# FoneAstra3_2.net
KiCad netlist of a schematic drawn in EAGLE
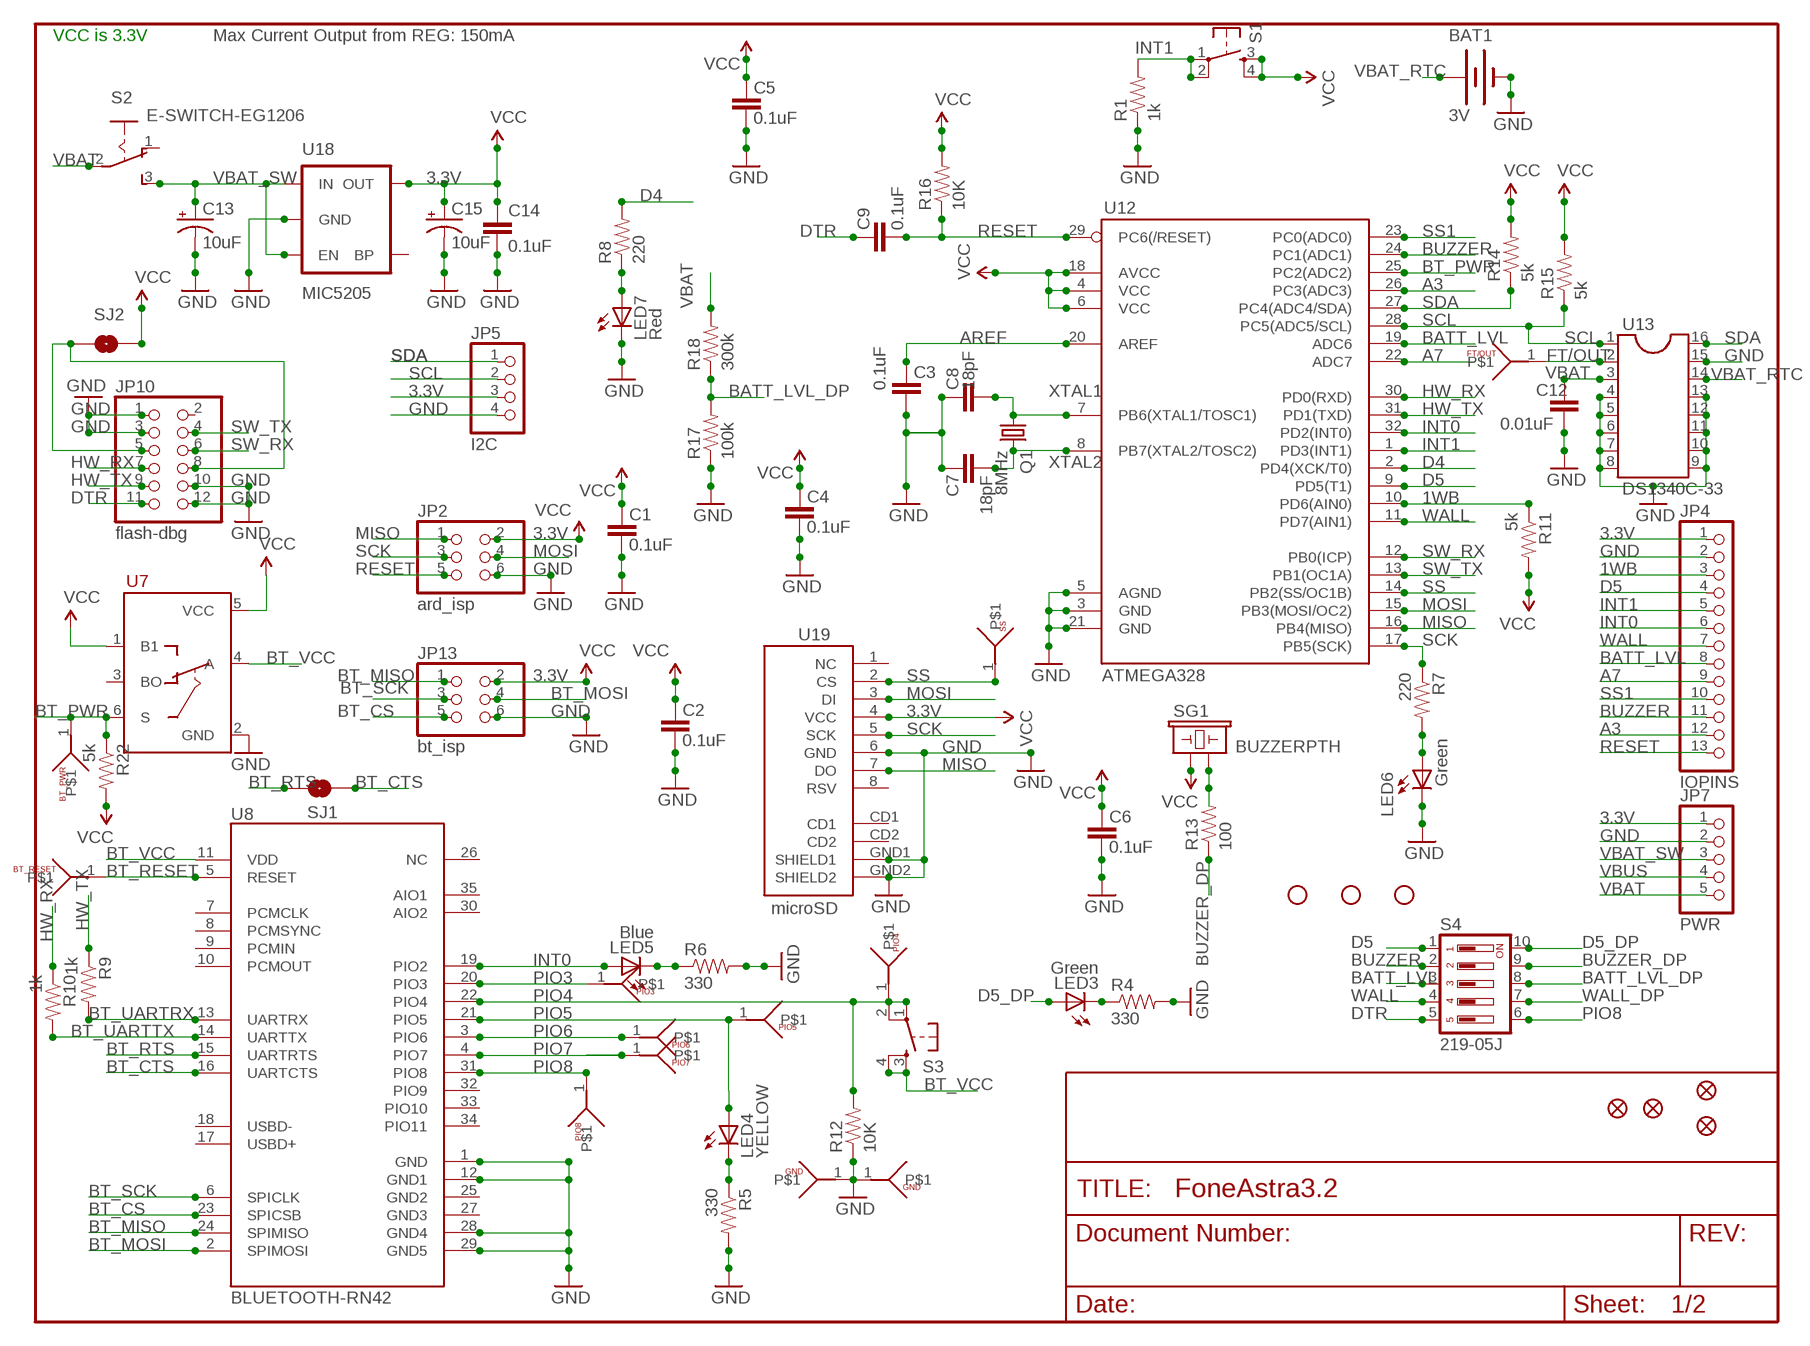
[diagram p0: schematic, sheet 1, part 1 of 2]
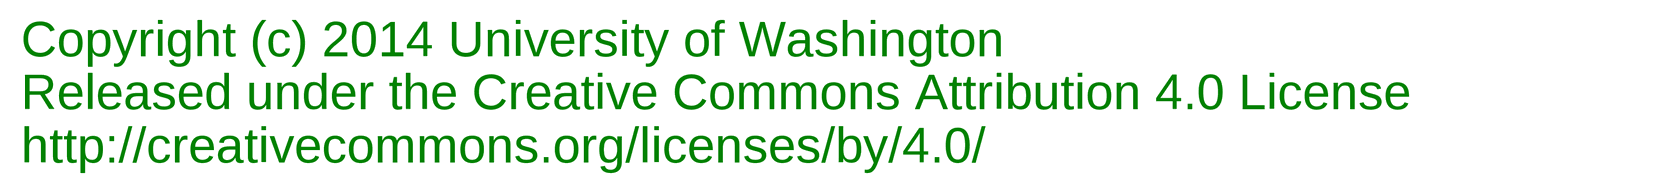
[diagram p1: schematic, sheet 1, part 2 of 2]
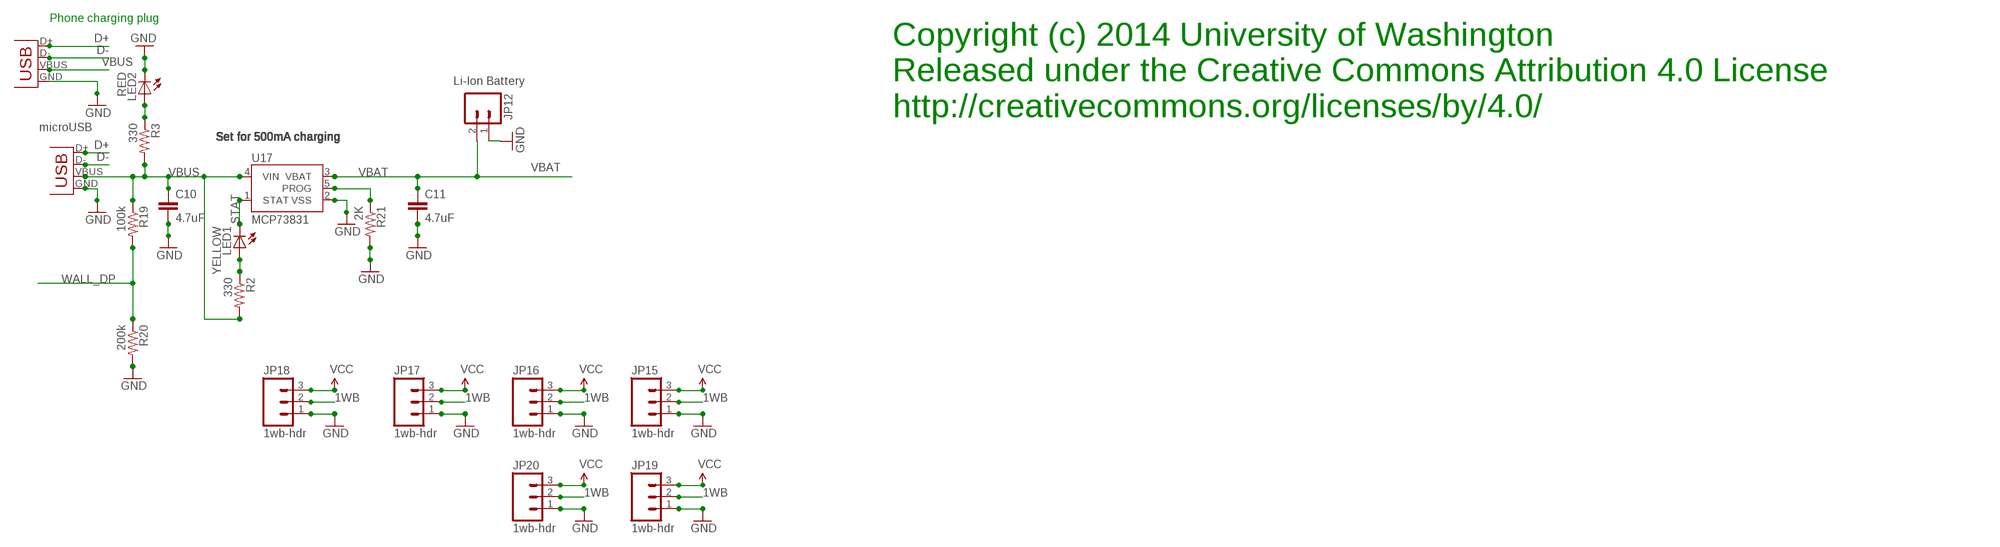
[diagram p2: schematic, sheet 2]

(export (version "E")
  (design (tool "Eeschema 10.0.6"))
  (components
    (comp (ref "C10")
      (value "4.7uF")
      (footprint "eagle-import:0402-CAP")
      (libsource (lib "eagle-import") (part "CAP0402-CAP"))
    )
    (comp (ref "C11")
      (value "4.7uF")
      (footprint "eagle-import:0402-CAP")
      (libsource (lib "eagle-import") (part "CAP0402-CAP"))
    )
    (comp (ref "JP12")
      (value "Li-Ion Battery")
      (footprint "eagle-import:SPARKFUN_JST-2-PTH")
      (libsource (lib "eagle-import") (part "SPARKFUN_M02JST-PTH-2"))
    )
    (comp (ref "JP15")
      (value "1wb-hdr")
      (footprint "eagle-import:JST-3-PTH")
      (libsource (lib "eagle-import") (part "M03JST-PTH"))
    )
    (comp (ref "JP16")
      (value "1wb-hdr")
      (footprint "eagle-import:JST-3-PTH")
      (libsource (lib "eagle-import") (part "M03JST-PTH"))
    )
    (comp (ref "JP17")
      (value "1wb-hdr")
      (footprint "eagle-import:JST-3-PTH")
      (libsource (lib "eagle-import") (part "M03JST-PTH"))
    )
    (comp (ref "JP18")
      (value "1wb-hdr")
      (footprint "eagle-import:JST-3-PTH")
      (libsource (lib "eagle-import") (part "M03JST-PTH"))
    )
    (comp (ref "JP19")
      (value "1wb-hdr")
      (footprint "eagle-import:JST-3-PTH")
      (libsource (lib "eagle-import") (part "M03JST-PTH"))
    )
    (comp (ref "JP20")
      (value "1wb-hdr")
      (footprint "eagle-import:JST-3-PTH")
      (libsource (lib "eagle-import") (part "M03JST-PTH"))
    )
    (comp (ref "LED1")
      (value "YELLOW")
      (footprint "eagle-import:LED-0603")
      (libsource (lib "eagle-import") (part "LED0603"))
    )
    (comp (ref "LED2")
      (value "RED")
      (footprint "eagle-import:LED-0603")
      (libsource (lib "eagle-import") (part "LED0603"))
    )
    (comp (ref "R2")
      (value "330")
      (footprint "eagle-import:0402-RES")
      (libsource (lib "eagle-import") (part "RESISTOR0402-RES"))
    )
    (comp (ref "R3")
      (value "330")
      (footprint "eagle-import:0402-RES")
      (libsource (lib "eagle-import") (part "RESISTOR0402-RES"))
    )
    (comp (ref "R19")
      (value "100k")
      (footprint "eagle-import:0402-RES")
      (libsource (lib "eagle-import") (part "RESISTOR0402-RES"))
    )
    (comp (ref "R20")
      (value "200k")
      (footprint "eagle-import:0402-RES")
      (libsource (lib "eagle-import") (part "RESISTOR0402-RES"))
    )
    (comp (ref "R21")
      (value "2K")
      (footprint "eagle-import:0402-RES")
      (libsource (lib "eagle-import") (part "RESISTOR0402-RES"))
    )
    (comp (ref "U17")
      (value "MCP73831")
      (footprint "eagle-import:SOT23-5")
      (libsource (lib "eagle-import") (part "MCP73831"))
    )
    (comp (ref "X1")
      (value "Micro USB")
      (footprint "eagle-import:USB-MICROB")
      (libsource (lib "eagle-import") (part "USB-MICROB"))
    )
    (comp (ref "X2")
      (value "Micro USB")
      (footprint "eagle-import:USB-MICROB")
      (libsource (lib "eagle-import") (part "USB-MICROB"))
    )
    (comp (ref "$$U3")
      (value "BT_RESET")
      (footprint "eagle-import:TESTPOINT")
      (libsource (lib "eagle-import") (part "TESTPOINT"))
    )
    (comp (ref "$$U4")
      (value "PIO6")
      (footprint "eagle-import:TESTPOINT")
      (libsource (lib "eagle-import") (part "TESTPOINT"))
    )
    (comp (ref "$$U5")
      (value "PIO7")
      (footprint "eagle-import:TESTPOINT")
      (libsource (lib "eagle-import") (part "TESTPOINT"))
    )
    (comp (ref "$$U6")
      (value "GND")
      (footprint "eagle-import:TESTPOINT")
      (libsource (lib "eagle-import") (part "TESTPOINT"))
    )
    (comp (ref "$$U9")
      (value "PIO4")
      (footprint "eagle-import:TESTPOINT")
      (libsource (lib "eagle-import") (part "TESTPOINT"))
    )
    (comp (ref "$$U10")
      (value "PIO3")
      (footprint "eagle-import:TESTPOINT")
      (libsource (lib "eagle-import") (part "TESTPOINT"))
    )
    (comp (ref "$$U11")
      (value "PIO5")
      (footprint "eagle-import:TESTPOINT")
      (libsource (lib "eagle-import") (part "TESTPOINT"))
    )
    (comp (ref "$$U15")
      (value "FT/OUT")
      (footprint "eagle-import:TESTPOINT")
      (libsource (lib "eagle-import") (part "TESTPOINT"))
    )
    (comp (ref "$$U16")
      (value "GND")
      (footprint "eagle-import:TESTPOINT")
      (libsource (lib "eagle-import") (part "TESTPOINT"))
    )
    (comp (ref "BAT1")
      (value "3V")
      (footprint "eagle-import:BATTCON_12MM_CURVED")
      (libsource (lib "eagle-import") (part "BATTERY"))
    )
    (comp (ref "BT_PWR")
      (value "BT_PWR")
      (footprint "eagle-import:TESTPOINT")
      (libsource (lib "eagle-import") (part "TESTPOINT"))
    )
    (comp (ref "C1")
      (value "0.1uF")
      (footprint "eagle-import:0402-CAP")
      (libsource (lib "eagle-import") (part "CAP0402-CAP"))
    )
    (comp (ref "C2")
      (value "0.1uF")
      (footprint "eagle-import:0402-CAP")
      (libsource (lib "eagle-import") (part "CAP0402-CAP"))
    )
    (comp (ref "C3")
      (value "0.1uF")
      (footprint "eagle-import:0402-CAP")
      (libsource (lib "eagle-import") (part "CAP0402-CAP"))
    )
    (comp (ref "C4")
      (value "0.1uF")
      (footprint "eagle-import:0402-CAP")
      (libsource (lib "eagle-import") (part "CAP0402-CAP"))
    )
    (comp (ref "C5")
      (value "0.1uF")
      (footprint "eagle-import:0402-CAP")
      (libsource (lib "eagle-import") (part "CAP0402-CAP"))
    )
    (comp (ref "C6")
      (value "0.1uF")
      (footprint "eagle-import:0402-CAP")
      (libsource (lib "eagle-import") (part "CAP0402-CAP"))
    )
    (comp (ref "C7")
      (value "18pF")
      (footprint "eagle-import:0402-CAP")
      (libsource (lib "eagle-import") (part "CAP0402-CAP"))
    )
    (comp (ref "C8")
      (value "18pF")
      (footprint "eagle-import:0402-CAP")
      (libsource (lib "eagle-import") (part "CAP0402-CAP"))
    )
    (comp (ref "C9")
      (value "0.1uF")
      (footprint "eagle-import:0402-CAP")
      (libsource (lib "eagle-import") (part "CAP0402-CAP"))
    )
    (comp (ref "C12")
      (value "0.01uF")
      (footprint "eagle-import:0402-CAP")
      (libsource (lib "eagle-import") (part "CAP0402-CAP"))
    )
    (comp (ref "C13")
      (value "10uF")
      (footprint "eagle-import:EIA3216")
      (libsource (lib "eagle-import") (part "CAP_POL1206"))
    )
    (comp (ref "C14")
      (value "0.1uF")
      (footprint "eagle-import:0402-CAP")
      (libsource (lib "eagle-import") (part "CAP0402-CAP"))
    )
    (comp (ref "C15")
      (value "10uF")
      (footprint "eagle-import:EIA3216")
      (libsource (lib "eagle-import") (part "CAP_POL1206"))
    )
    (comp (ref "JP1")
      (value "SPARKFUN_FIDUCIAL1.5X3")
      (footprint "eagle-import:SPARKFUN_FIDUCIAL-1.5X3")
      (libsource (lib "eagle-import") (part "SPARKFUN_FIDUCIAL1.5X3"))
    )
    (comp (ref "JP2")
      (value "ard_isp")
      (footprint "eagle-import:2X03")
      (libsource (lib "eagle-import") (part "PINHD-2X3"))
    )
    (comp (ref "JP3")
      (value "STAND-OFFTIGHT")
      (footprint "eagle-import:STAND-OFF-TIGHT")
      (libsource (lib "eagle-import") (part "STAND-OFFTIGHT"))
    )
    (comp (ref "JP4")
      (value "IOPINS")
      (footprint "eagle-import:1X13M")
      (libsource (lib "eagle-import") (part "PINHD-1X13M"))
    )
    (comp (ref "JP5")
      (value "I2C")
      (footprint "eagle-import:1X04M")
      (libsource (lib "eagle-import") (part "PINHD-1X4M"))
    )
    (comp (ref "JP6")
      (value "STAND-OFFTIGHT")
      (footprint "eagle-import:STAND-OFF-TIGHT")
      (libsource (lib "eagle-import") (part "STAND-OFFTIGHT"))
    )
    (comp (ref "JP7")
      (value "PWR")
      (footprint "eagle-import:1X05M")
      (libsource (lib "eagle-import") (part "PINHD-1X5M"))
    )
    (comp (ref "JP8")
      (value "SPARKFUN_FIDUCIAL1.5X3")
      (footprint "eagle-import:SPARKFUN_FIDUCIAL-1.5X3")
      (libsource (lib "eagle-import") (part "SPARKFUN_FIDUCIAL1.5X3"))
    )
    (comp (ref "JP9")
      (value "STAND-OFFTIGHT")
      (footprint "eagle-import:STAND-OFF-TIGHT")
      (libsource (lib "eagle-import") (part "STAND-OFFTIGHT"))
    )
    (comp (ref "JP10")
      (value "flash-dbg")
      (footprint "eagle-import:2X06")
      (libsource (lib "eagle-import") (part "PINHD-2X6"))
    )
    (comp (ref "JP11")
      (value "SPARKFUN_FIDUCIAL1.5X3")
      (footprint "eagle-import:SPARKFUN_FIDUCIAL-1.5X3")
      (libsource (lib "eagle-import") (part "SPARKFUN_FIDUCIAL1.5X3"))
    )
    (comp (ref "JP13")
      (value "bt_isp")
      (footprint "eagle-import:2X03")
      (libsource (lib "eagle-import") (part "PINHD-2X3"))
    )
    (comp (ref "JP14")
      (value "SPARKFUN_FIDUCIAL1.5X3")
      (footprint "eagle-import:SPARKFUN_FIDUCIAL-1.5X3")
      (libsource (lib "eagle-import") (part "SPARKFUN_FIDUCIAL1.5X3"))
    )
    (comp (ref "LED3")
      (value "Green")
      (footprint "eagle-import:LED-0603")
      (libsource (lib "eagle-import") (part "LED0603"))
    )
    (comp (ref "LED4")
      (value "YELLOW")
      (footprint "eagle-import:LED-0603")
      (libsource (lib "eagle-import") (part "LED0603"))
    )
    (comp (ref "LED5")
      (value "Blue")
      (footprint "eagle-import:LED-0603")
      (libsource (lib "eagle-import") (part "LED0603"))
    )
    (comp (ref "LED6")
      (value "Green")
      (footprint "eagle-import:LED-0603")
      (libsource (lib "eagle-import") (part "LED0603"))
    )
    (comp (ref "LED7")
      (value "Red")
      (footprint "eagle-import:LED-0603")
      (libsource (lib "eagle-import") (part "LED0603"))
    )
    (comp (ref "PIO8")
      (value "PIO8")
      (footprint "eagle-import:TESTPOINT")
      (libsource (lib "eagle-import") (part "TESTPOINT"))
    )
    (comp (ref "Q1")
      (value "8MHz")
      (footprint "eagle-import:HC49_S")
      (libsource (lib "eagle-import") (part "CRYSTALHC49S"))
    )
    (comp (ref "R1")
      (value "1k")
      (footprint "eagle-import:0402-RES")
      (libsource (lib "eagle-import") (part "RESISTOR0402-RES"))
    )
    (comp (ref "R4")
      (value "330")
      (footprint "eagle-import:0402-RES")
      (libsource (lib "eagle-import") (part "RESISTOR0402-RES"))
    )
    (comp (ref "R5")
      (value "330")
      (footprint "eagle-import:0402-RES")
      (libsource (lib "eagle-import") (part "RESISTOR0402-RES"))
    )
    (comp (ref "R6")
      (value "330")
      (footprint "eagle-import:0402-RES")
      (libsource (lib "eagle-import") (part "RESISTOR0402-RES"))
    )
    (comp (ref "R7")
      (value "220")
      (footprint "eagle-import:0402-RES")
      (libsource (lib "eagle-import") (part "RESISTOR0402-RES"))
    )
    (comp (ref "R8")
      (value "220")
      (footprint "eagle-import:0402-RES")
      (libsource (lib "eagle-import") (part "RESISTOR0402-RES"))
    )
    (comp (ref "R9")
      (value "1k")
      (footprint "eagle-import:0402-RES")
      (libsource (lib "eagle-import") (part "RESISTOR0402-RES"))
    )
    (comp (ref "R10")
      (value "1k")
      (footprint "eagle-import:0402-RES")
      (libsource (lib "eagle-import") (part "RESISTOR0402-RES"))
    )
    (comp (ref "R11")
      (value "5k")
      (footprint "eagle-import:0402-RES")
      (libsource (lib "eagle-import") (part "RESISTOR0402-RES"))
    )
    (comp (ref "R12")
      (value "10K")
      (footprint "eagle-import:0402-RES")
      (libsource (lib "eagle-import") (part "RESISTOR0402-RES"))
    )
    (comp (ref "R13")
      (value "100")
      (footprint "eagle-import:0402-RES")
      (libsource (lib "eagle-import") (part "RESISTOR0402-RES"))
    )
    (comp (ref "R14")
      (value "5k")
      (footprint "eagle-import:0402-RES")
      (libsource (lib "eagle-import") (part "RESISTOR0402-RES"))
    )
    (comp (ref "R15")
      (value "5k")
      (footprint "eagle-import:0402-RES")
      (libsource (lib "eagle-import") (part "RESISTOR0402-RES"))
    )
    (comp (ref "R16")
      (value "10K")
      (footprint "eagle-import:0402-RES")
      (libsource (lib "eagle-import") (part "RESISTOR0402-RES"))
    )
    (comp (ref "R17")
      (value "100k")
      (footprint "eagle-import:0402-RES")
      (libsource (lib "eagle-import") (part "RESISTOR0402-RES"))
    )
    (comp (ref "R18")
      (value "300k")
      (footprint "eagle-import:0402-RES")
      (libsource (lib "eagle-import") (part "RESISTOR0402-RES"))
    )
    (comp (ref "R22")
      (value "5k")
      (footprint "eagle-import:0402-RES")
      (libsource (lib "eagle-import") (part "RESISTOR0402-RES"))
    )
    (comp (ref "S1")
      (value "switch")
      (footprint "eagle-import:SPARKFUN_TACTILE-PTH")
      (libsource (lib "eagle-import") (part "SPARKFUN_TAC_SWITCHPTH"))
    )
    (comp (ref "S2")
      (value "E-SWITCH-EG1206")
      (footprint "eagle-import:EG1206")
      (libsource (lib "eagle-import") (part "E-SWITCH-EG1206"))
    )
    (comp (ref "S3")
      (value "Reset")
      (footprint "eagle-import:TACTILE_SWITCH_SMD")
      (libsource (lib "eagle-import") (part "TAC_SWITCHSMD"))
    )
    (comp (ref "S4")
      (value "219-05J")
      (footprint "eagle-import:CTS-219-05J")
      (libsource (lib "eagle-import") (part "219-05J"))
    )
    (comp (ref "SG1")
      (value "BUZZERPTH")
      (footprint "eagle-import:BUZZER-12MM")
      (libsource (lib "eagle-import") (part "BUZZERPTH"))
    )
    (comp (ref "SJ1")
      (value "SOLDERJUMPERNC2")
      (footprint "eagle-import:SJ_2S-NOTRACE")
      (libsource (lib "eagle-import") (part "SOLDERJUMPERNC2"))
    )
    (comp (ref "SJ2")
      (value "SOLDERJUMPERNC2")
      (footprint "eagle-import:SJ_2S-NOTRACE")
      (libsource (lib "eagle-import") (part "SOLDERJUMPERNC2"))
    )
    (comp (ref "SS")
      (value "SS")
      (footprint "eagle-import:TESTPOINT")
      (libsource (lib "eagle-import") (part "TESTPOINT"))
    )
    (comp (ref "U7")
      (value "FSA4157AP6X")
      (footprint "eagle-import:SC70-6")
      (libsource (lib "eagle-import") (part "FSA4157AP6X"))
    )
    (comp (ref "U8")
      (value "BLUETOOTH-RN42")
      (footprint "eagle-import:RN41")
      (libsource (lib "eagle-import") (part "BLUETOOTH-RN41{dblquote}"))
    )
    (comp (ref "U12")
      (value "ATMEGA328")
      (footprint "eagle-import:TQFP32-08")
      (libsource (lib "eagle-import") (part "ATMEGA168"))
    )
    (comp (ref "U13")
      (value "DS1340C-33")
      (footprint "eagle-import:SO16L")
      (libsource (lib "eagle-import") (part "DS1340C-33"))
    )
    (comp (ref "U18")
      (value "MIC5205")
      (footprint "eagle-import:SOT23-5")
      (libsource (lib "eagle-import") (part "V_REG_LDOSMD"))
    )
    (comp (ref "U19")
      (value "microSD")
      (footprint "eagle-import:MICRO-SD-SOCKET-PP")
      (libsource (lib "eagle-import") (part "USD-SOCKETSMD"))
    )
  )
  (nets
    (net (code "1") (name "1WB") (class "Default")
      (node (ref "JP15") (pin "2") (pinfunction "2_2") (pintype "passive"))
      (node (ref "JP16") (pin "2") (pinfunction "2_2") (pintype "passive"))
      (node (ref "JP17") (pin "2") (pinfunction "2_2") (pintype "passive"))
      (node (ref "JP18") (pin "2") (pinfunction "2_2") (pintype "passive"))
      (node (ref "JP19") (pin "2") (pinfunction "2_2") (pintype "passive"))
      (node (ref "JP20") (pin "2") (pinfunction "2_2") (pintype "passive"))
      (node (ref "JP4") (pin "3") (pinfunction "3_3") (pintype "passive"))
      (node (ref "R11") (pin "1") (pinfunction "1_1") (pintype "passive"))
      (node (ref "U12") (pin "10") (pinfunction "PD6(AIN0)_10") (pintype "bidirectional"))
    )
    (net (code "2") (name "3.3V") (class "Default")
      (node (ref "C1") (pin "2") (pinfunction "2_2") (pintype "passive"))
      (node (ref "C14") (pin "1") (pinfunction "1_1") (pintype "passive"))
      (node (ref "C15") (pin "A") (pinfunction "+_A") (pintype "passive"))
      (node (ref "C2") (pin "2") (pinfunction "2_2") (pintype "passive"))
      (node (ref "C4") (pin "2") (pinfunction "2_2") (pintype "passive"))
      (node (ref "C5") (pin "2") (pinfunction "2_2") (pintype "passive"))
      (node (ref "C6") (pin "2") (pinfunction "2_2") (pintype "passive"))
      (node (ref "JP13") (pin "2") (pinfunction "2_2") (pintype "passive"))
      (node (ref "JP15") (pin "3") (pinfunction "3_3") (pintype "passive"))
      (node (ref "JP16") (pin "3") (pinfunction "3_3") (pintype "passive"))
      (node (ref "JP17") (pin "3") (pinfunction "3_3") (pintype "passive"))
      (node (ref "JP18") (pin "3") (pinfunction "3_3") (pintype "passive"))
      (node (ref "JP19") (pin "3") (pinfunction "3_3") (pintype "passive"))
      (node (ref "JP2") (pin "2") (pinfunction "2_2") (pintype "passive"))
      (node (ref "JP20") (pin "3") (pinfunction "3_3") (pintype "passive"))
      (node (ref "JP4") (pin "1") (pinfunction "1_1") (pintype "passive"))
      (node (ref "JP5") (pin "3") (pinfunction "3_3") (pintype "passive"))
      (node (ref "JP7") (pin "1") (pinfunction "1_1") (pintype "passive"))
      (node (ref "R11") (pin "2") (pinfunction "2_2") (pintype "passive"))
      (node (ref "R14") (pin "2") (pinfunction "2_2") (pintype "passive"))
      (node (ref "R15") (pin "2") (pinfunction "2_2") (pintype "passive"))
      (node (ref "R16") (pin "2") (pinfunction "2_2") (pintype "passive"))
      (node (ref "R22") (pin "2") (pinfunction "2_2") (pintype "passive"))
      (node (ref "S1") (pin "3") (pinfunction "3_3") (pintype "passive"))
      (node (ref "S1") (pin "4") (pinfunction "4_4") (pintype "passive"))
      (node (ref "SG1") (pin "+") (pinfunction "1_+") (pintype "passive"))
      (node (ref "SJ2") (pin "1") (pinfunction "1_1") (pintype "passive"))
      (node (ref "U12") (pin "18") (pinfunction "AVCC_18") (pintype "bidirectional"))
      (node (ref "U12") (pin "4") (pinfunction "VCC_4") (pintype "bidirectional"))
      (node (ref "U12") (pin "6") (pinfunction "VCC_6") (pintype "bidirectional"))
      (node (ref "U18") (pin "5") (pinfunction "OUT_5") (pintype "passive"))
      (node (ref "U19") (pin "4") (pinfunction "VCC_4") (pintype "bidirectional"))
      (node (ref "U7") (pin "1") (pinfunction "B1_1") (pintype "passive"))
      (node (ref "U7") (pin "5") (pinfunction "VCC_5") (pintype "power_in"))
    )
    (net (code "3") (name "A3") (class "Default")
      (node (ref "JP4") (pin "12") (pinfunction "12_12") (pintype "passive"))
      (node (ref "U12") (pin "26") (pinfunction "PC3(ADC3)_26") (pintype "bidirectional"))
    )
    (net (code "4") (name "A7") (class "Default")
      (node (ref "JP4") (pin "9") (pinfunction "9_9") (pintype "passive"))
      (node (ref "U12") (pin "22") (pinfunction "ADC7_22") (pintype "bidirectional"))
    )
    (net (code "5") (name "AREF") (class "Default")
      (node (ref "C3") (pin "2") (pinfunction "2_2") (pintype "passive"))
      (node (ref "U12") (pin "20") (pinfunction "AREF_20") (pintype "bidirectional"))
    )
    (net (code "6") (name "BATT_LVL") (class "Default")
      (node (ref "JP4") (pin "8") (pinfunction "8_8") (pintype "passive"))
      (node (ref "S4") (pin "3") (pinfunction "3_3") (pintype "passive"))
      (node (ref "U12") (pin "19") (pinfunction "ADC6_19") (pintype "bidirectional"))
    )
    (net (code "7") (name "BATT_LVL_DP") (class "Default")
      (node (ref "R17") (pin "2") (pinfunction "2_2") (pintype "passive"))
      (node (ref "R18") (pin "1") (pinfunction "1_1") (pintype "passive"))
      (node (ref "S4") (pin "8") (pinfunction "8_8") (pintype "passive"))
    )
    (net (code "8") (name "BT_CS") (class "Default")
      (node (ref "JP13") (pin "5") (pinfunction "5_5") (pintype "passive"))
      (node (ref "U8") (pin "23") (pinfunction "SPICSB_23") (pintype "bidirectional"))
    )
    (net (code "9") (name "BT_CTS") (class "Default")
      (node (ref "SJ1") (pin "1") (pinfunction "1_1") (pintype "passive"))
      (node (ref "U8") (pin "16") (pinfunction "UARTCTS_16") (pintype "bidirectional"))
    )
    (net (code "10") (name "BT_MISO") (class "Default")
      (node (ref "JP13") (pin "1") (pinfunction "1_1") (pintype "passive"))
      (node (ref "U8") (pin "24") (pinfunction "SPIMISO_24") (pintype "bidirectional"))
    )
    (net (code "11") (name "BT_MOSI") (class "Default")
      (node (ref "JP13") (pin "4") (pinfunction "4_4") (pintype "passive"))
      (node (ref "U8") (pin "2") (pinfunction "SPIMOSI_2") (pintype "bidirectional"))
    )
    (net (code "12") (name "BT_PWR") (class "Default")
      (node (ref "BT_PWR") (pin "1") (pinfunction "P$1_1") (pintype "bidirectional"))
      (node (ref "R22") (pin "1") (pinfunction "1_1") (pintype "passive"))
      (node (ref "U12") (pin "25") (pinfunction "PC2(ADC2)_25") (pintype "bidirectional"))
      (node (ref "U7") (pin "6") (pinfunction "S_6") (pintype "bidirectional"))
    )
    (net (code "13") (name "BT_RESET") (class "Default")
      (node (ref "$$U3") (pin "1") (pinfunction "P$1_1") (pintype "bidirectional"))
      (node (ref "U8") (pin "5") (pinfunction "RESET_5") (pintype "bidirectional"))
    )
    (net (code "14") (name "BT_RTS") (class "Default")
      (node (ref "SJ1") (pin "2") (pinfunction "2_2") (pintype "passive"))
      (node (ref "U8") (pin "15") (pinfunction "UARTRTS_15") (pintype "bidirectional"))
    )
    (net (code "15") (name "BT_SCK") (class "Default")
      (node (ref "JP13") (pin "3") (pinfunction "3_3") (pintype "passive"))
      (node (ref "U8") (pin "6") (pinfunction "SPICLK_6") (pintype "bidirectional"))
    )
    (net (code "16") (name "BT_UARTRX") (class "Default")
      (node (ref "R9") (pin "2") (pinfunction "2_2") (pintype "passive"))
      (node (ref "U8") (pin "13") (pinfunction "UARTRX_13") (pintype "bidirectional"))
    )
    (net (code "17") (name "BT_UARTTX") (class "Default")
      (node (ref "R10") (pin "2") (pinfunction "2_2") (pintype "passive"))
      (node (ref "U8") (pin "14") (pinfunction "UARTTX_14") (pintype "bidirectional"))
    )
    (net (code "18") (name "BT_VCC") (class "Default")
      (node (ref "S3") (pin "3") (pinfunction "3_3") (pintype "passive"))
      (node (ref "S3") (pin "4") (pinfunction "4_4") (pintype "passive"))
      (node (ref "U7") (pin "4") (pinfunction "A_4") (pintype "passive"))
      (node (ref "U8") (pin "11") (pinfunction "VDD_11") (pintype "bidirectional"))
    )
    (net (code "19") (name "BUZZER") (class "Default")
      (node (ref "JP4") (pin "11") (pinfunction "11_11") (pintype "passive"))
      (node (ref "S4") (pin "2") (pinfunction "2_2") (pintype "passive"))
      (node (ref "U12") (pin "24") (pinfunction "PC1(ADC1)_24") (pintype "bidirectional"))
    )
    (net (code "20") (name "BUZZER_DP") (class "Default")
      (node (ref "R13") (pin "1") (pinfunction "1_1") (pintype "passive"))
      (node (ref "S4") (pin "9") (pinfunction "9_9") (pintype "passive"))
    )
    (net (code "21") (name "D+") (class "Default")
      (node (ref "X1") (pin "D+") (pinfunction "D+_D+") (pintype "bidirectional"))
      (node (ref "X2") (pin "D+") (pinfunction "D+_D+") (pintype "bidirectional"))
    )
    (net (code "22") (name "D-") (class "Default")
      (node (ref "X1") (pin "D-") (pinfunction "D-_D-") (pintype "bidirectional"))
      (node (ref "X2") (pin "D-") (pinfunction "D-_D-") (pintype "bidirectional"))
    )
    (net (code "23") (name "D4") (class "Default")
      (node (ref "R8") (pin "2") (pinfunction "2_2") (pintype "passive"))
      (node (ref "U12") (pin "2") (pinfunction "PD4(XCK/T0)_2") (pintype "bidirectional"))
    )
    (net (code "24") (name "D5") (class "Default")
      (node (ref "JP4") (pin "4") (pinfunction "4_4") (pintype "passive"))
      (node (ref "S4") (pin "1") (pinfunction "1_1") (pintype "passive"))
      (node (ref "U12") (pin "9") (pinfunction "PD5(T1)_9") (pintype "bidirectional"))
    )
    (net (code "25") (name "D5_DP") (class "Default")
      (node (ref "LED3") (pin "A") (pinfunction "A_A") (pintype "passive"))
      (node (ref "S4") (pin "10") (pinfunction "10_10") (pintype "passive"))
    )
    (net (code "26") (name "DTR") (class "Default")
      (node (ref "C9") (pin "2") (pinfunction "2_2") (pintype "passive"))
      (node (ref "JP10") (pin "11") (pinfunction "11_11") (pintype "passive"))
      (node (ref "S4") (pin "5") (pinfunction "5_5") (pintype "passive"))
    )
    (net (code "27") (name "FT{slash}OUT") (class "Default")
      (node (ref "$$U15") (pin "1") (pinfunction "P$1_1") (pintype "bidirectional"))
      (node (ref "U13") (pin "2") (pinfunction "2_2") (pintype "passive"))
    )
    (net (code "28") (name "GND") (class "Default")
      (node (ref "$$U16") (pin "1") (pinfunction "P$1_1") (pintype "bidirectional"))
      (node (ref "$$U6") (pin "1") (pinfunction "P$1_1") (pintype "bidirectional"))
      (node (ref "BAT1") (pin "GND") (pinfunction "-_GND") (pintype "power_in"))
      (node (ref "C1") (pin "1") (pinfunction "1_1") (pintype "passive"))
      (node (ref "C10") (pin "2") (pinfunction "2_2") (pintype "passive"))
      (node (ref "C11") (pin "2") (pinfunction "2_2") (pintype "passive"))
      (node (ref "C12") (pin "1") (pinfunction "1_1") (pintype "passive"))
      (node (ref "C13") (pin "C") (pinfunction "-_C") (pintype "passive"))
      (node (ref "C14") (pin "2") (pinfunction "2_2") (pintype "passive"))
      (node (ref "C15") (pin "C") (pinfunction "-_C") (pintype "passive"))
      (node (ref "C2") (pin "1") (pinfunction "1_1") (pintype "passive"))
      (node (ref "C3") (pin "1") (pinfunction "1_1") (pintype "passive"))
      (node (ref "C4") (pin "1") (pinfunction "1_1") (pintype "passive"))
      (node (ref "C5") (pin "1") (pinfunction "1_1") (pintype "passive"))
      (node (ref "C6") (pin "1") (pinfunction "1_1") (pintype "passive"))
      (node (ref "C7") (pin "2") (pinfunction "2_2") (pintype "passive"))
      (node (ref "C8") (pin "2") (pinfunction "2_2") (pintype "passive"))
      (node (ref "JP10") (pin "1") (pinfunction "1_1") (pintype "passive"))
      (node (ref "JP10") (pin "10") (pinfunction "10_10") (pintype "passive"))
      (node (ref "JP10") (pin "12") (pinfunction "12_12") (pintype "passive"))
      (node (ref "JP10") (pin "3") (pinfunction "3_3") (pintype "passive"))
      (node (ref "JP12") (pin "1") (pinfunction "1_1") (pintype "passive"))
      (node (ref "JP13") (pin "6") (pinfunction "6_6") (pintype "passive"))
      (node (ref "JP15") (pin "1") (pinfunction "1_1") (pintype "passive"))
      (node (ref "JP16") (pin "1") (pinfunction "1_1") (pintype "passive"))
      (node (ref "JP17") (pin "1") (pinfunction "1_1") (pintype "passive"))
      (node (ref "JP18") (pin "1") (pinfunction "1_1") (pintype "passive"))
      (node (ref "JP19") (pin "1") (pinfunction "1_1") (pintype "passive"))
      (node (ref "JP2") (pin "6") (pinfunction "6_6") (pintype "passive"))
      (node (ref "JP20") (pin "1") (pinfunction "1_1") (pintype "passive"))
      (node (ref "JP4") (pin "2") (pinfunction "2_2") (pintype "passive"))
      (node (ref "JP5") (pin "4") (pinfunction "4_4") (pintype "passive"))
      (node (ref "JP7") (pin "2") (pinfunction "2_2") (pintype "passive"))
      (node (ref "LED2") (pin "C") (pinfunction "C_C") (pintype "passive"))
      (node (ref "LED6") (pin "C") (pinfunction "C_C") (pintype "passive"))
      (node (ref "LED7") (pin "C") (pinfunction "C_C") (pintype "passive"))
      (node (ref "R1") (pin "1") (pinfunction "1_1") (pintype "passive"))
      (node (ref "R12") (pin "1") (pinfunction "1_1") (pintype "passive"))
      (node (ref "R17") (pin "1") (pinfunction "1_1") (pintype "passive"))
      (node (ref "R20") (pin "2") (pinfunction "2_2") (pintype "passive"))
      (node (ref "R21") (pin "2") (pinfunction "2_2") (pintype "passive"))
      (node (ref "R4") (pin "2") (pinfunction "2_2") (pintype "passive"))
      (node (ref "R5") (pin "2") (pinfunction "2_2") (pintype "passive"))
      (node (ref "R6") (pin "2") (pinfunction "2_2") (pintype "passive"))
      (node (ref "U12") (pin "21") (pinfunction "GND_21") (pintype "bidirectional"))
      (node (ref "U12") (pin "3") (pinfunction "GND_3") (pintype "bidirectional"))
      (node (ref "U12") (pin "5") (pinfunction "AGND_5") (pintype "bidirectional"))
      (node (ref "U13") (pin "10") (pinfunction "10_10") (pintype "passive"))
      (node (ref "U13") (pin "11") (pinfunction "11_11") (pintype "passive"))
      (node (ref "U13") (pin "12") (pinfunction "12_12") (pintype "passive"))
      (node (ref "U13") (pin "13") (pinfunction "13_13") (pintype "passive"))
      (node (ref "U13") (pin "15") (pinfunction "15_15") (pintype "passive"))
      (node (ref "U13") (pin "4") (pinfunction "4_4") (pintype "passive"))
      (node (ref "U13") (pin "5") (pinfunction "5_5") (pintype "passive"))
      (node (ref "U13") (pin "6") (pinfunction "6_6") (pintype "passive"))
      (node (ref "U13") (pin "7") (pinfunction "7_7") (pintype "passive"))
      (node (ref "U13") (pin "8") (pinfunction "8_8") (pintype "passive"))
      (node (ref "U13") (pin "9") (pinfunction "9_9") (pintype "passive"))
      (node (ref "U17") (pin "2") (pinfunction "VSS_2") (pintype "power_in"))
      (node (ref "U18") (pin "2") (pinfunction "GND_2") (pintype "input"))
      (node (ref "U19") (pin "6") (pinfunction "GND_6") (pintype "bidirectional"))
      (node (ref "U19") (pin "GND1") (pinfunction "SHIELD1_GND1") (pintype "bidirectional"))
      (node (ref "U19") (pin "GND2") (pinfunction "SHIELD2_GND2") (pintype "bidirectional"))
      (node (ref "U7") (pin "2") (pinfunction "GND_2") (pintype "bidirectional"))
      (node (ref "U8") (pin "1") (pinfunction "GND_1") (pintype "bidirectional"))
      (node (ref "U8") (pin "12") (pinfunction "GND1_12") (pintype "bidirectional"))
      (node (ref "U8") (pin "28") (pinfunction "GND4_28") (pintype "bidirectional"))
      (node (ref "U8") (pin "29") (pinfunction "GND5_29") (pintype "bidirectional"))
      (node (ref "X1") (pin "GND") (pinfunction "GND_GND") (pintype "bidirectional"))
      (node (ref "X2") (pin "GND") (pinfunction "GND_GND") (pintype "bidirectional"))
    )
    (net (code "29") (name "HW_RX") (class "Default")
      (node (ref "JP10") (pin "7") (pinfunction "7_7") (pintype "passive"))
      (node (ref "R10") (pin "1") (pinfunction "1_1") (pintype "passive"))
      (node (ref "U12") (pin "30") (pinfunction "PD0(RXD)_30") (pintype "bidirectional"))
    )
    (net (code "30") (name "HW_TX") (class "Default")
      (node (ref "JP10") (pin "9") (pinfunction "9_9") (pintype "passive"))
      (node (ref "R9") (pin "1") (pinfunction "1_1") (pintype "passive"))
      (node (ref "U12") (pin "31") (pinfunction "PD1(TXD)_31") (pintype "bidirectional"))
    )
    (net (code "31") (name "INT0") (class "Default")
      (node (ref "JP4") (pin "6") (pinfunction "6_6") (pintype "passive"))
      (node (ref "LED5") (pin "A") (pinfunction "A_A") (pintype "passive"))
      (node (ref "U12") (pin "32") (pinfunction "PD2(INT0)_32") (pintype "bidirectional"))
      (node (ref "U8") (pin "19") (pinfunction "PIO2_19") (pintype "bidirectional"))
    )
    (net (code "32") (name "INT1") (class "Default")
      (node (ref "JP4") (pin "5") (pinfunction "5_5") (pintype "passive"))
      (node (ref "R1") (pin "2") (pinfunction "2_2") (pintype "passive"))
      (node (ref "S1") (pin "1") (pinfunction "1_1") (pintype "passive"))
      (node (ref "S1") (pin "2") (pinfunction "2_2") (pintype "passive"))
      (node (ref "U12") (pin "1") (pinfunction "PD3(INT1)_1") (pintype "bidirectional"))
    )
    (net (code "33") (name "MISO") (class "Default")
      (node (ref "JP2") (pin "1") (pinfunction "1_1") (pintype "passive"))
      (node (ref "U12") (pin "16") (pinfunction "PB4(MISO)_16") (pintype "bidirectional"))
      (node (ref "U19") (pin "7") (pinfunction "DO_7") (pintype "bidirectional"))
    )
    (net (code "34") (name "MOSI") (class "Default")
      (node (ref "JP2") (pin "4") (pinfunction "4_4") (pintype "passive"))
      (node (ref "U12") (pin "15") (pinfunction "PB3(MOSI/OC2)_15") (pintype "bidirectional"))
      (node (ref "U19") (pin "3") (pinfunction "DI_3") (pintype "bidirectional"))
    )
    (net (code "35") (name "Net-(JP10-Pad5)") (class "Default")
      (node (ref "JP10") (pin "5") (pinfunction "5_5") (pintype "passive"))
      (node (ref "JP10") (pin "8") (pinfunction "8_8") (pintype "passive"))
      (node (ref "SJ2") (pin "2") (pinfunction "2_2") (pintype "passive"))
    )
    (net (code "36") (name "Net-(LED1-PadA)") (class "Default")
      (node (ref "LED1") (pin "A") (pinfunction "A_A") (pintype "passive"))
      (node (ref "R2") (pin "1") (pinfunction "1_1") (pintype "passive"))
    )
    (net (code "37") (name "Net-(LED2-PadA)") (class "Default")
      (node (ref "LED2") (pin "A") (pinfunction "A_A") (pintype "passive"))
      (node (ref "R3") (pin "1") (pinfunction "1_1") (pintype "passive"))
    )
    (net (code "38") (name "Net-(LED3-PadC)") (class "Default")
      (node (ref "LED3") (pin "C") (pinfunction "C_C") (pintype "passive"))
      (node (ref "R4") (pin "1") (pinfunction "1_1") (pintype "passive"))
    )
    (net (code "39") (name "Net-(LED4-PadC)") (class "Default")
      (node (ref "LED4") (pin "C") (pinfunction "C_C") (pintype "passive"))
      (node (ref "R5") (pin "1") (pinfunction "1_1") (pintype "passive"))
    )
    (net (code "40") (name "Net-(LED5-PadC)") (class "Default")
      (node (ref "LED5") (pin "C") (pinfunction "C_C") (pintype "passive"))
      (node (ref "R6") (pin "1") (pinfunction "1_1") (pintype "passive"))
    )
    (net (code "41") (name "Net-(LED6-PadA)") (class "Default")
      (node (ref "LED6") (pin "A") (pinfunction "A_A") (pintype "passive"))
      (node (ref "R7") (pin "2") (pinfunction "2_2") (pintype "passive"))
    )
    (net (code "42") (name "Net-(LED7-PadA)") (class "Default")
      (node (ref "LED7") (pin "A") (pinfunction "A_A") (pintype "passive"))
      (node (ref "R8") (pin "1") (pinfunction "1_1") (pintype "passive"))
    )
    (net (code "43") (name "Net-(SG1-2)") (class "Default")
      (node (ref "R13") (pin "2") (pinfunction "2_2") (pintype "passive"))
      (node (ref "SG1") (pin "-") (pinfunction "2_-") (pintype "passive"))
    )
    (net (code "44") (name "Net-(U17-PROG)") (class "Default")
      (node (ref "R21") (pin "1") (pinfunction "1_1") (pintype "passive"))
      (node (ref "U17") (pin "5") (pinfunction "PROG_5") (pintype "input"))
    )
    (net (code "45") (name "PIO3") (class "Default")
      (node (ref "$$U10") (pin "1") (pinfunction "P$1_1") (pintype "bidirectional"))
      (node (ref "U8") (pin "20") (pinfunction "PIO3_20") (pintype "bidirectional"))
    )
    (net (code "46") (name "PIO4") (class "Default")
      (node (ref "$$U9") (pin "1") (pinfunction "P$1_1") (pintype "bidirectional"))
      (node (ref "R12") (pin "2") (pinfunction "2_2") (pintype "passive"))
      (node (ref "S3") (pin "1") (pinfunction "1_1") (pintype "passive"))
      (node (ref "S3") (pin "2") (pinfunction "2_2") (pintype "passive"))
      (node (ref "U8") (pin "22") (pinfunction "PIO4_22") (pintype "bidirectional"))
    )
    (net (code "47") (name "PIO5") (class "Default")
      (node (ref "$$U11") (pin "1") (pinfunction "P$1_1") (pintype "bidirectional"))
      (node (ref "LED4") (pin "A") (pinfunction "A_A") (pintype "passive"))
      (node (ref "U8") (pin "21") (pinfunction "PIO5_21") (pintype "bidirectional"))
    )
    (net (code "48") (name "PIO6") (class "Default")
      (node (ref "$$U4") (pin "1") (pinfunction "P$1_1") (pintype "bidirectional"))
      (node (ref "U8") (pin "3") (pinfunction "PIO6_3") (pintype "bidirectional"))
    )
    (net (code "49") (name "PIO7") (class "Default")
      (node (ref "$$U5") (pin "1") (pinfunction "P$1_1") (pintype "bidirectional"))
      (node (ref "U8") (pin "4") (pinfunction "PIO7_4") (pintype "bidirectional"))
    )
    (net (code "50") (name "PIO8") (class "Default")
      (node (ref "PIO8") (pin "1") (pinfunction "P$1_1") (pintype "bidirectional"))
      (node (ref "S4") (pin "6") (pinfunction "6_6") (pintype "passive"))
      (node (ref "U8") (pin "31") (pinfunction "PIO8_31") (pintype "bidirectional"))
    )
    (net (code "51") (name "RESET") (class "Default")
      (node (ref "C9") (pin "1") (pinfunction "1_1") (pintype "passive"))
      (node (ref "JP2") (pin "5") (pinfunction "5_5") (pintype "passive"))
      (node (ref "JP4") (pin "13") (pinfunction "13_13") (pintype "passive"))
      (node (ref "R16") (pin "1") (pinfunction "1_1") (pintype "passive"))
      (node (ref "U12") (pin "29") (pinfunction "PC6(/RESET)_29") (pintype "bidirectional"))
    )
    (net (code "52") (name "SCK") (class "Default")
      (node (ref "JP2") (pin "3") (pinfunction "3_3") (pintype "passive"))
      (node (ref "R7") (pin "1") (pinfunction "1_1") (pintype "passive"))
      (node (ref "U12") (pin "17") (pinfunction "PB5(SCK)_17") (pintype "bidirectional"))
      (node (ref "U19") (pin "5") (pinfunction "SCK_5") (pintype "bidirectional"))
    )
    (net (code "53") (name "SCL") (class "Default")
      (node (ref "JP5") (pin "2") (pinfunction "2_2") (pintype "passive"))
      (node (ref "R15") (pin "1") (pinfunction "1_1") (pintype "passive"))
      (node (ref "U12") (pin "28") (pinfunction "PC5(ADC5/SCL)_28") (pintype "bidirectional"))
      (node (ref "U13") (pin "1") (pinfunction "1_1") (pintype "passive"))
    )
    (net (code "54") (name "SDA") (class "Default")
      (node (ref "JP5") (pin "1") (pinfunction "1_1") (pintype "passive"))
      (node (ref "R14") (pin "1") (pinfunction "1_1") (pintype "passive"))
      (node (ref "U12") (pin "27") (pinfunction "PC4(ADC4/SDA)_27") (pintype "bidirectional"))
      (node (ref "U13") (pin "16") (pinfunction "16_16") (pintype "passive"))
    )
    (net (code "55") (name "SS") (class "Default")
      (node (ref "SS") (pin "1") (pinfunction "P$1_1") (pintype "bidirectional"))
      (node (ref "U12") (pin "14") (pinfunction "PB2(SS/OC1B)_14") (pintype "bidirectional"))
      (node (ref "U19") (pin "2") (pinfunction "CS_2") (pintype "bidirectional"))
    )
    (net (code "56") (name "SS1") (class "Default")
      (node (ref "JP4") (pin "10") (pinfunction "10_10") (pintype "passive"))
      (node (ref "U12") (pin "23") (pinfunction "PC0(ADC0)_23") (pintype "bidirectional"))
    )
    (net (code "57") (name "STAT") (class "Default")
      (node (ref "LED1") (pin "C") (pinfunction "C_C") (pintype "passive"))
      (node (ref "U17") (pin "1") (pinfunction "STAT_1") (pintype "output"))
    )
    (net (code "58") (name "SW_RX") (class "Default")
      (node (ref "JP10") (pin "6") (pinfunction "6_6") (pintype "passive"))
      (node (ref "U12") (pin "12") (pinfunction "PB0(ICP)_12") (pintype "bidirectional"))
    )
    (net (code "59") (name "SW_TX") (class "Default")
      (node (ref "JP10") (pin "4") (pinfunction "4_4") (pintype "passive"))
      (node (ref "U12") (pin "13") (pinfunction "PB1(OC1A)_13") (pintype "bidirectional"))
    )
    (net (code "60") (name "VBAT") (class "Default")
      (node (ref "C11") (pin "1") (pinfunction "1_1") (pintype "passive"))
      (node (ref "C12") (pin "2") (pinfunction "2_2") (pintype "passive"))
      (node (ref "JP12") (pin "2") (pinfunction "2_2") (pintype "passive"))
      (node (ref "JP7") (pin "5") (pinfunction "5_5") (pintype "passive"))
      (node (ref "R18") (pin "2") (pinfunction "2_2") (pintype "passive"))
      (node (ref "S2") (pin "2") (pinfunction "P_2") (pintype "passive"))
      (node (ref "U13") (pin "3") (pinfunction "3_3") (pintype "passive"))
      (node (ref "U17") (pin "3") (pinfunction "VBAT_3") (pintype "power_in"))
    )
    (net (code "61") (name "VBAT_RTC") (class "Default")
      (node (ref "BAT1") (pin "PWR@1") (pinfunction "+_PWR@1") (pintype "power_in"))
      (node (ref "U13") (pin "14") (pinfunction "14_14") (pintype "passive"))
    )
    (net (code "62") (name "VBAT_SW") (class "Default")
      (node (ref "C13") (pin "A") (pinfunction "+_A") (pintype "passive"))
      (node (ref "JP7") (pin "3") (pinfunction "3_3") (pintype "passive"))
      (node (ref "S2") (pin "3") (pinfunction "S_3") (pintype "passive"))
      (node (ref "U18") (pin "1") (pinfunction "IN_1") (pintype "input"))
      (node (ref "U18") (pin "3") (pinfunction "EN_3") (pintype "input"))
    )
    (net (code "63") (name "VBUS") (class "Default")
      (node (ref "C10") (pin "1") (pinfunction "1_1") (pintype "passive"))
      (node (ref "JP7") (pin "4") (pinfunction "4_4") (pintype "passive"))
      (node (ref "R19") (pin "1") (pinfunction "1_1") (pintype "passive"))
      (node (ref "R2") (pin "2") (pinfunction "2_2") (pintype "passive"))
      (node (ref "R3") (pin "2") (pinfunction "2_2") (pintype "passive"))
      (node (ref "U17") (pin "4") (pinfunction "VIN_4") (pintype "power_in"))
      (node (ref "X1") (pin "VBUS") (pinfunction "VBUS_VBUS") (pintype "bidirectional"))
      (node (ref "X2") (pin "VBUS") (pinfunction "VBUS_VBUS") (pintype "bidirectional"))
    )
    (net (code "64") (name "WALL") (class "Default")
      (node (ref "JP4") (pin "7") (pinfunction "7_7") (pintype "passive"))
      (node (ref "S4") (pin "4") (pinfunction "4_4") (pintype "passive"))
      (node (ref "U12") (pin "11") (pinfunction "PD7(AIN1)_11") (pintype "bidirectional"))
    )
    (net (code "65") (name "WALL_DP") (class "Default")
      (node (ref "R19") (pin "2") (pinfunction "2_2") (pintype "passive"))
      (node (ref "R20") (pin "1") (pinfunction "1_1") (pintype "passive"))
      (node (ref "S4") (pin "7") (pinfunction "7_7") (pintype "passive"))
    )
    (net (code "66") (name "XTAL1") (class "Default")
      (node (ref "C8") (pin "1") (pinfunction "1_1") (pintype "passive"))
      (node (ref "Q1") (pin "1") (pinfunction "1_1") (pintype "passive"))
      (node (ref "U12") (pin "7") (pinfunction "PB6(XTAL1/TOSC1)_7") (pintype "bidirectional"))
    )
    (net (code "67") (name "XTAL2") (class "Default")
      (node (ref "C7") (pin "1") (pinfunction "1_1") (pintype "passive"))
      (node (ref "Q1") (pin "2") (pinfunction "2_2") (pintype "passive"))
      (node (ref "U12") (pin "8") (pinfunction "PB7(XTAL2/TOSC2)_8") (pintype "bidirectional"))
    )
    (net (code "68") (name "unconnected-(JP10-Pad2)") (class "Default")
      (node (ref "JP10") (pin "2") (pinfunction "2_2") (pintype "passive"))
    )
    (net (code "69") (name "unconnected-(S2-O-Pad1)") (class "Default")
      (node (ref "S2") (pin "1") (pinfunction "O_1") (pintype "passive"))
    )
    (net (code "70") (name "unconnected-(U7-BO-Pad3)") (class "Default")
      (node (ref "U7") (pin "3") (pinfunction "BO_3") (pintype "passive"))
    )
    (net (code "71") (name "unconnected-(U8-AIO1-Pad35)") (class "Default")
      (node (ref "U8") (pin "35") (pinfunction "AIO1_35") (pintype "bidirectional"))
    )
    (net (code "72") (name "unconnected-(U8-AIO2-Pad30)") (class "Default")
      (node (ref "U8") (pin "30") (pinfunction "AIO2_30") (pintype "bidirectional"))
    )
    (net (code "73") (name "unconnected-(U8-GND2-Pad25)") (class "Default")
      (node (ref "U8") (pin "25") (pinfunction "GND2_25") (pintype "bidirectional"))
    )
    (net (code "74") (name "unconnected-(U8-GND3-Pad27)") (class "Default")
      (node (ref "U8") (pin "27") (pinfunction "GND3_27") (pintype "bidirectional"))
    )
    (net (code "75") (name "unconnected-(U8-NC-Pad26)") (class "Default")
      (node (ref "U8") (pin "26") (pinfunction "NC_26") (pintype "bidirectional"))
    )
    (net (code "76") (name "unconnected-(U8-PCMCLK-Pad7)") (class "Default")
      (node (ref "U8") (pin "7") (pinfunction "PCMCLK_7") (pintype "bidirectional"))
    )
    (net (code "77") (name "unconnected-(U8-PCMIN-Pad9)") (class "Default")
      (node (ref "U8") (pin "9") (pinfunction "PCMIN_9") (pintype "bidirectional"))
    )
    (net (code "78") (name "unconnected-(U8-PCMOUT-Pad10)") (class "Default")
      (node (ref "U8") (pin "10") (pinfunction "PCMOUT_10") (pintype "bidirectional"))
    )
    (net (code "79") (name "unconnected-(U8-PCMSYNC-Pad8)") (class "Default")
      (node (ref "U8") (pin "8") (pinfunction "PCMSYNC_8") (pintype "bidirectional"))
    )
    (net (code "80") (name "unconnected-(U8-PIO9-Pad32)") (class "Default")
      (node (ref "U8") (pin "32") (pinfunction "PIO9_32") (pintype "bidirectional"))
    )
    (net (code "81") (name "unconnected-(U8-PIO10-Pad33)") (class "Default")
      (node (ref "U8") (pin "33") (pinfunction "PIO10_33") (pintype "bidirectional"))
    )
    (net (code "82") (name "unconnected-(U8-PIO11-Pad34)") (class "Default")
      (node (ref "U8") (pin "34") (pinfunction "PIO11_34") (pintype "bidirectional"))
    )
    (net (code "83") (name "unconnected-(U8-USBD+-Pad17)") (class "Default")
      (node (ref "U8") (pin "17") (pinfunction "USBD+_17") (pintype "bidirectional"))
    )
    (net (code "84") (name "unconnected-(U8-USBD--Pad18)") (class "Default")
      (node (ref "U8") (pin "18") (pinfunction "USBD-_18") (pintype "bidirectional"))
    )
    (net (code "85") (name "unconnected-(U18-BP-Pad4)") (class "Default")
      (node (ref "U18") (pin "4") (pinfunction "BP_4") (pintype "input"))
    )
    (net (code "86") (name "unconnected-(U19-NC-Pad1)") (class "Default")
      (node (ref "U19") (pin "1") (pinfunction "NC_1") (pintype "bidirectional"))
    )
    (net (code "87") (name "unconnected-(U19-PadCD1)") (class "Default")
      (node (ref "U19") (pin "CD1") (pinfunction "CD1_CD1") (pintype "bidirectional"))
    )
    (net (code "88") (name "unconnected-(U19-PadCD2)") (class "Default")
      (node (ref "U19") (pin "CD2") (pinfunction "CD2_CD2") (pintype "bidirectional"))
    )
    (net (code "89") (name "unconnected-(U19-RSV-Pad8)") (class "Default")
      (node (ref "U19") (pin "8") (pinfunction "RSV_8") (pintype "bidirectional"))
    )
  )
)
